# DAUGHTER_AUDIO.net
KiCad netlist of a schematic drawn in EAGLE
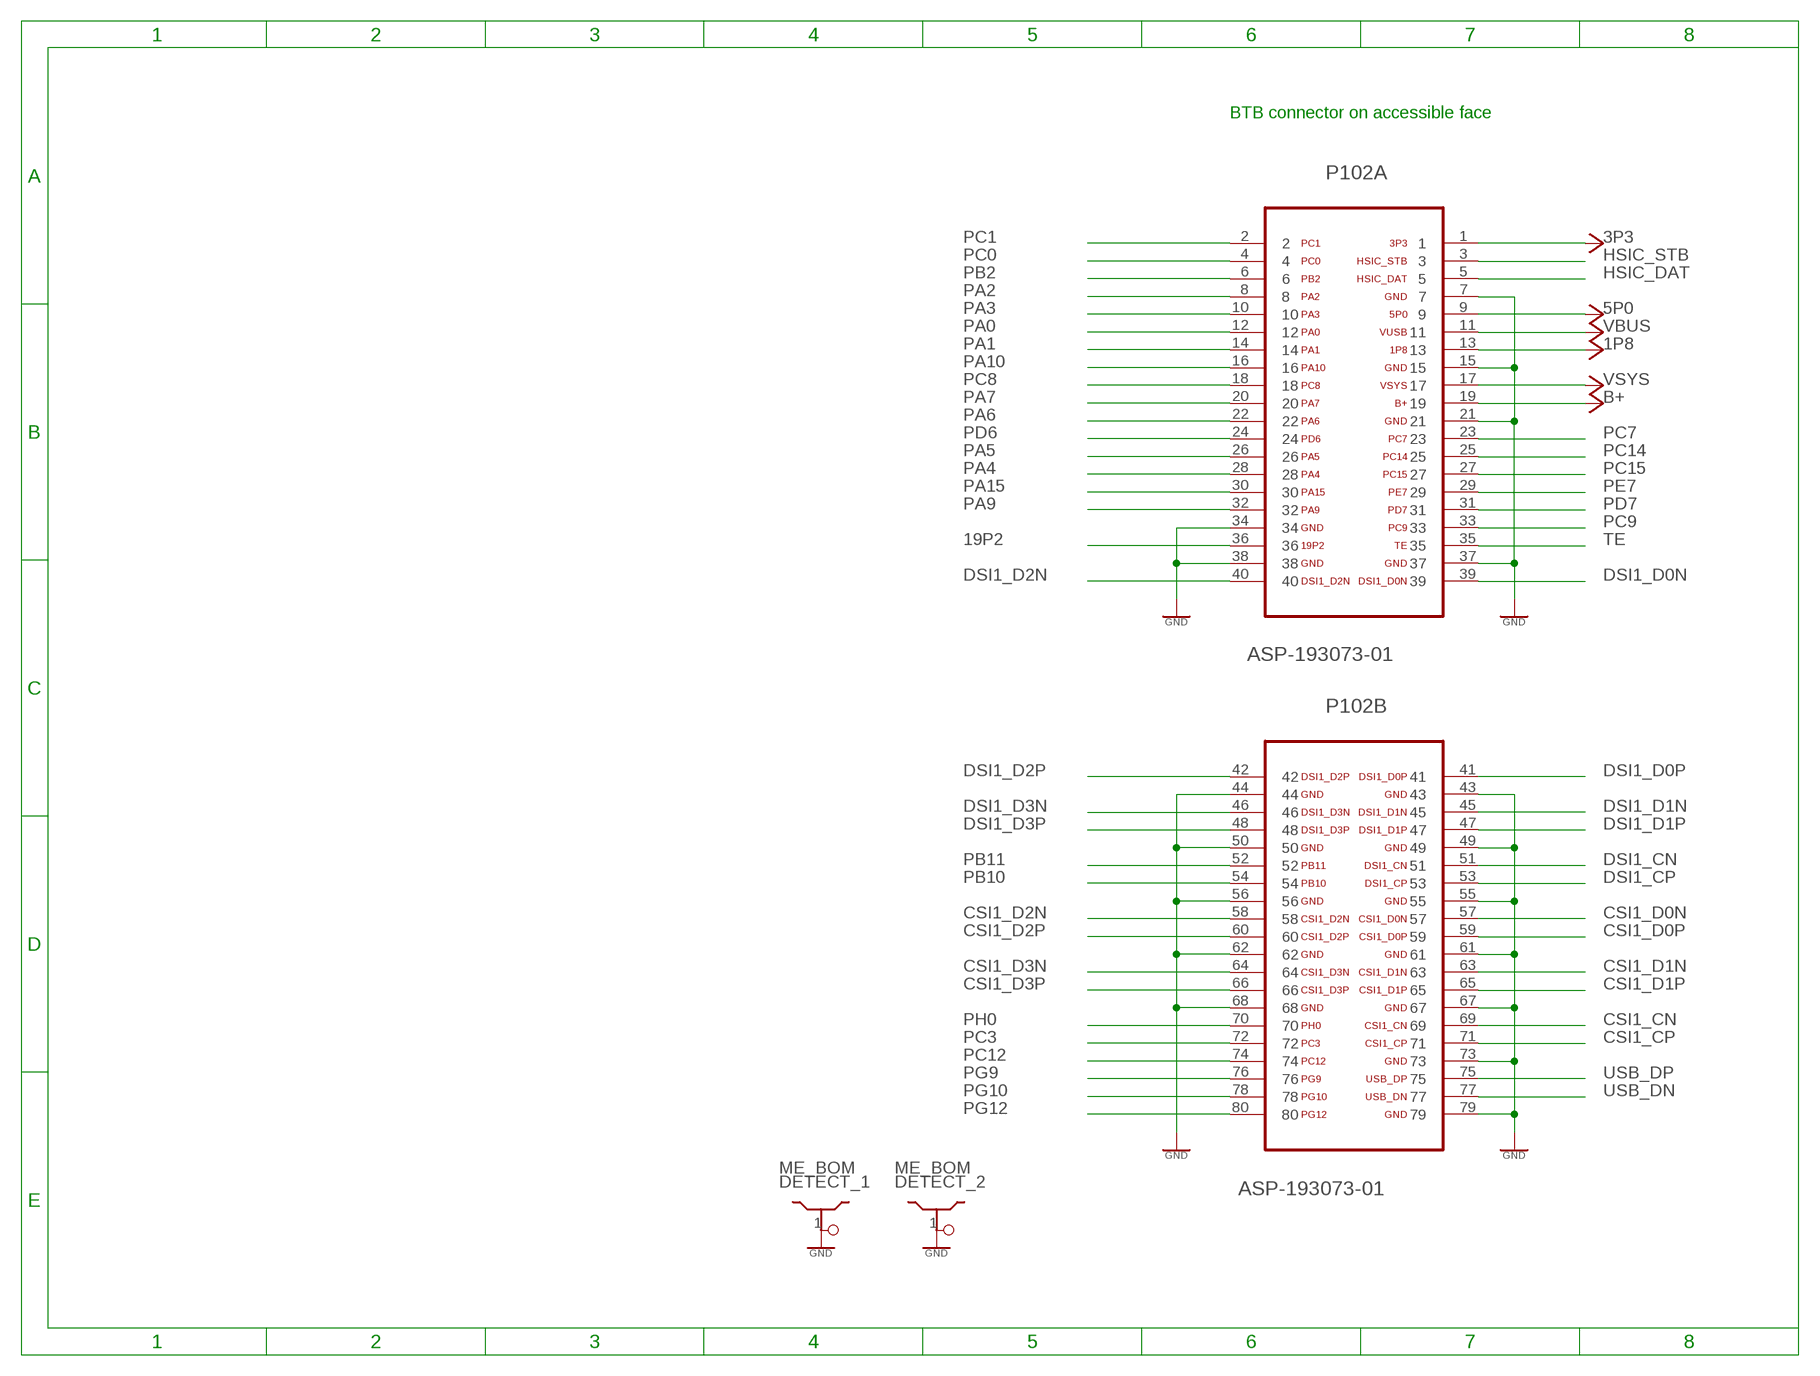
[diagram p0: schematic, sheet 1]
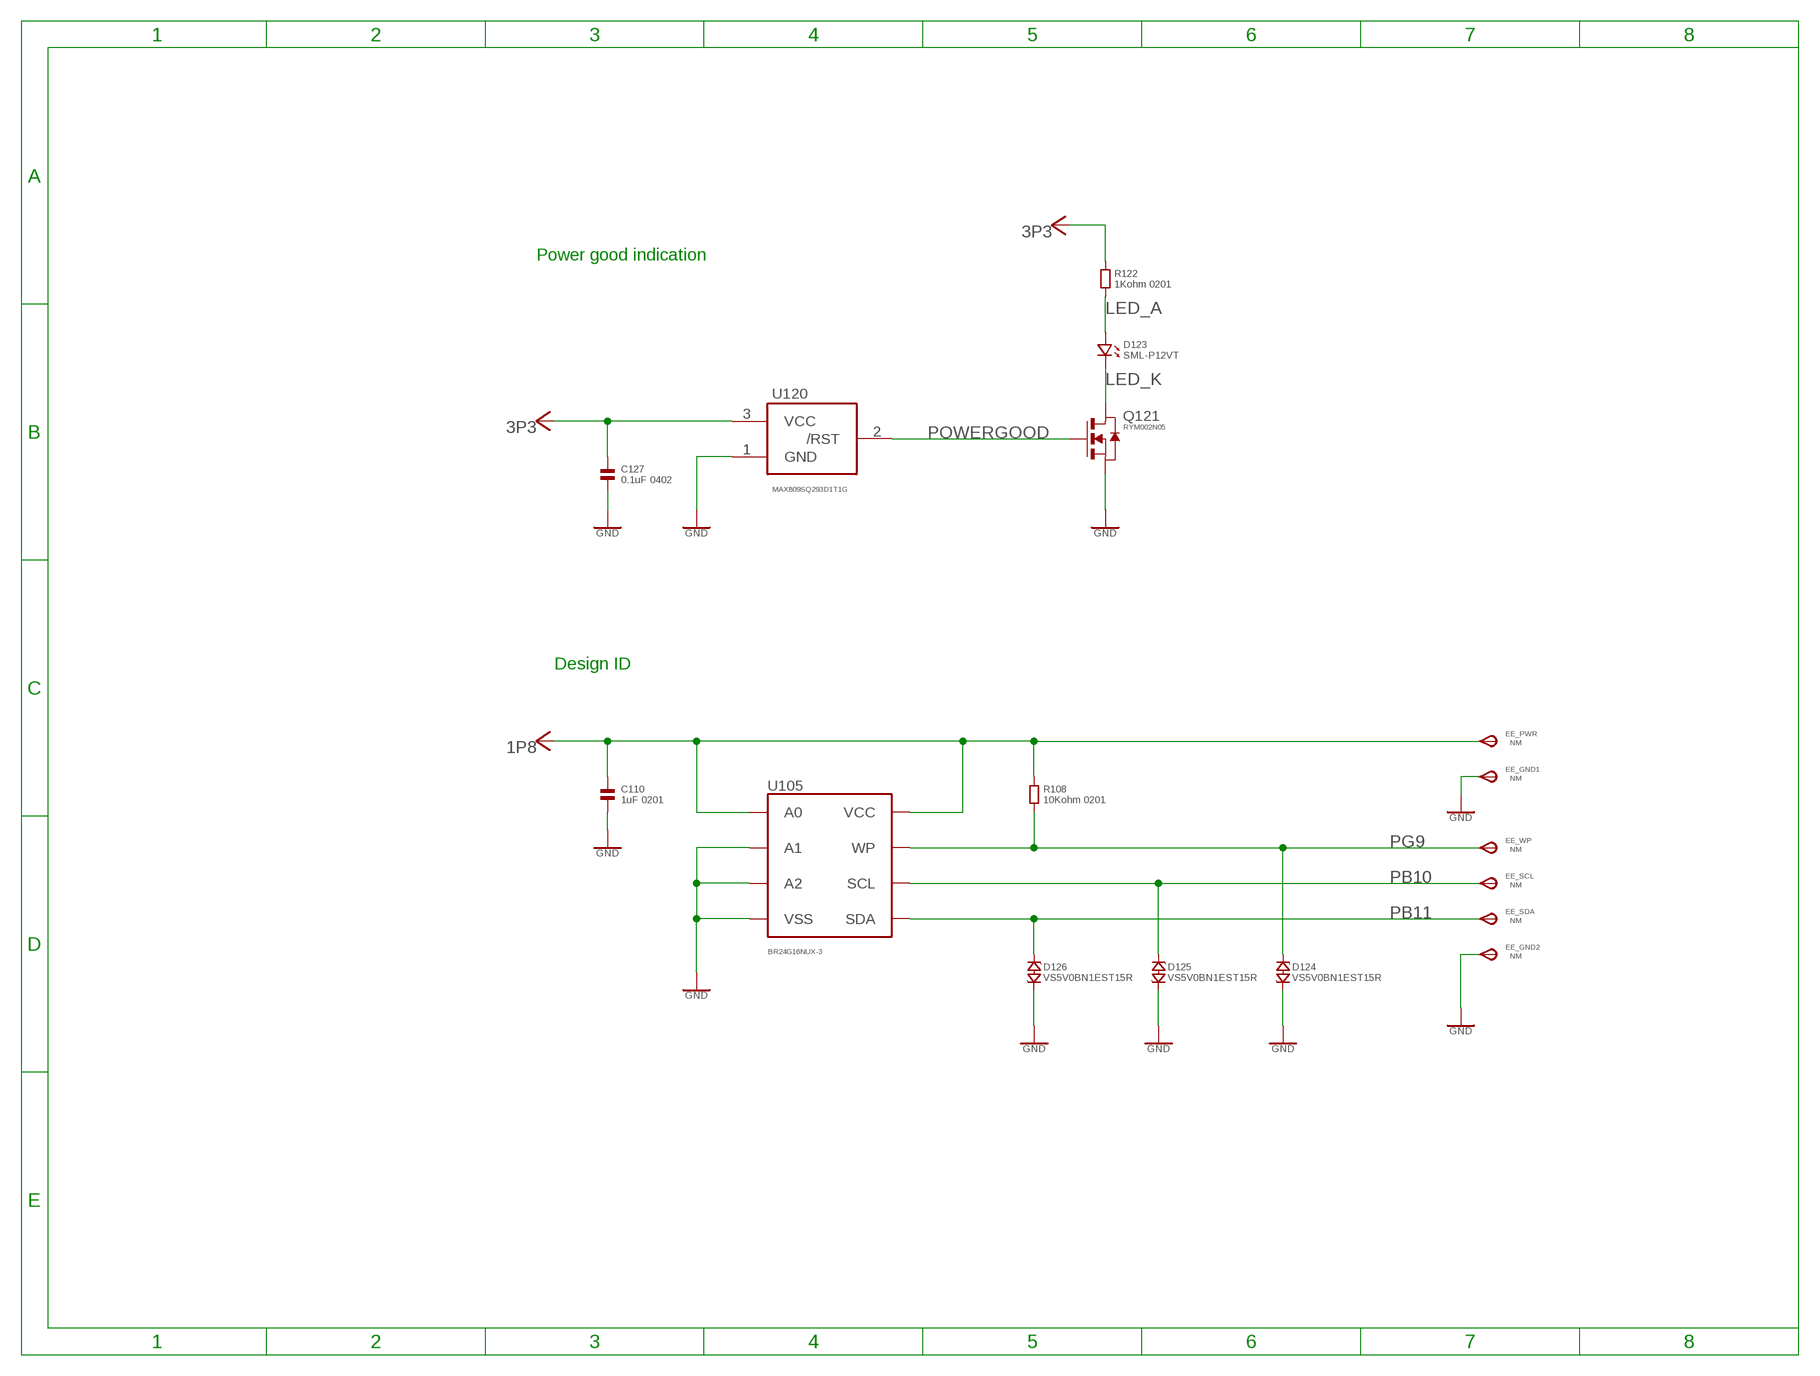
[diagram p1: schematic, sheet 2]
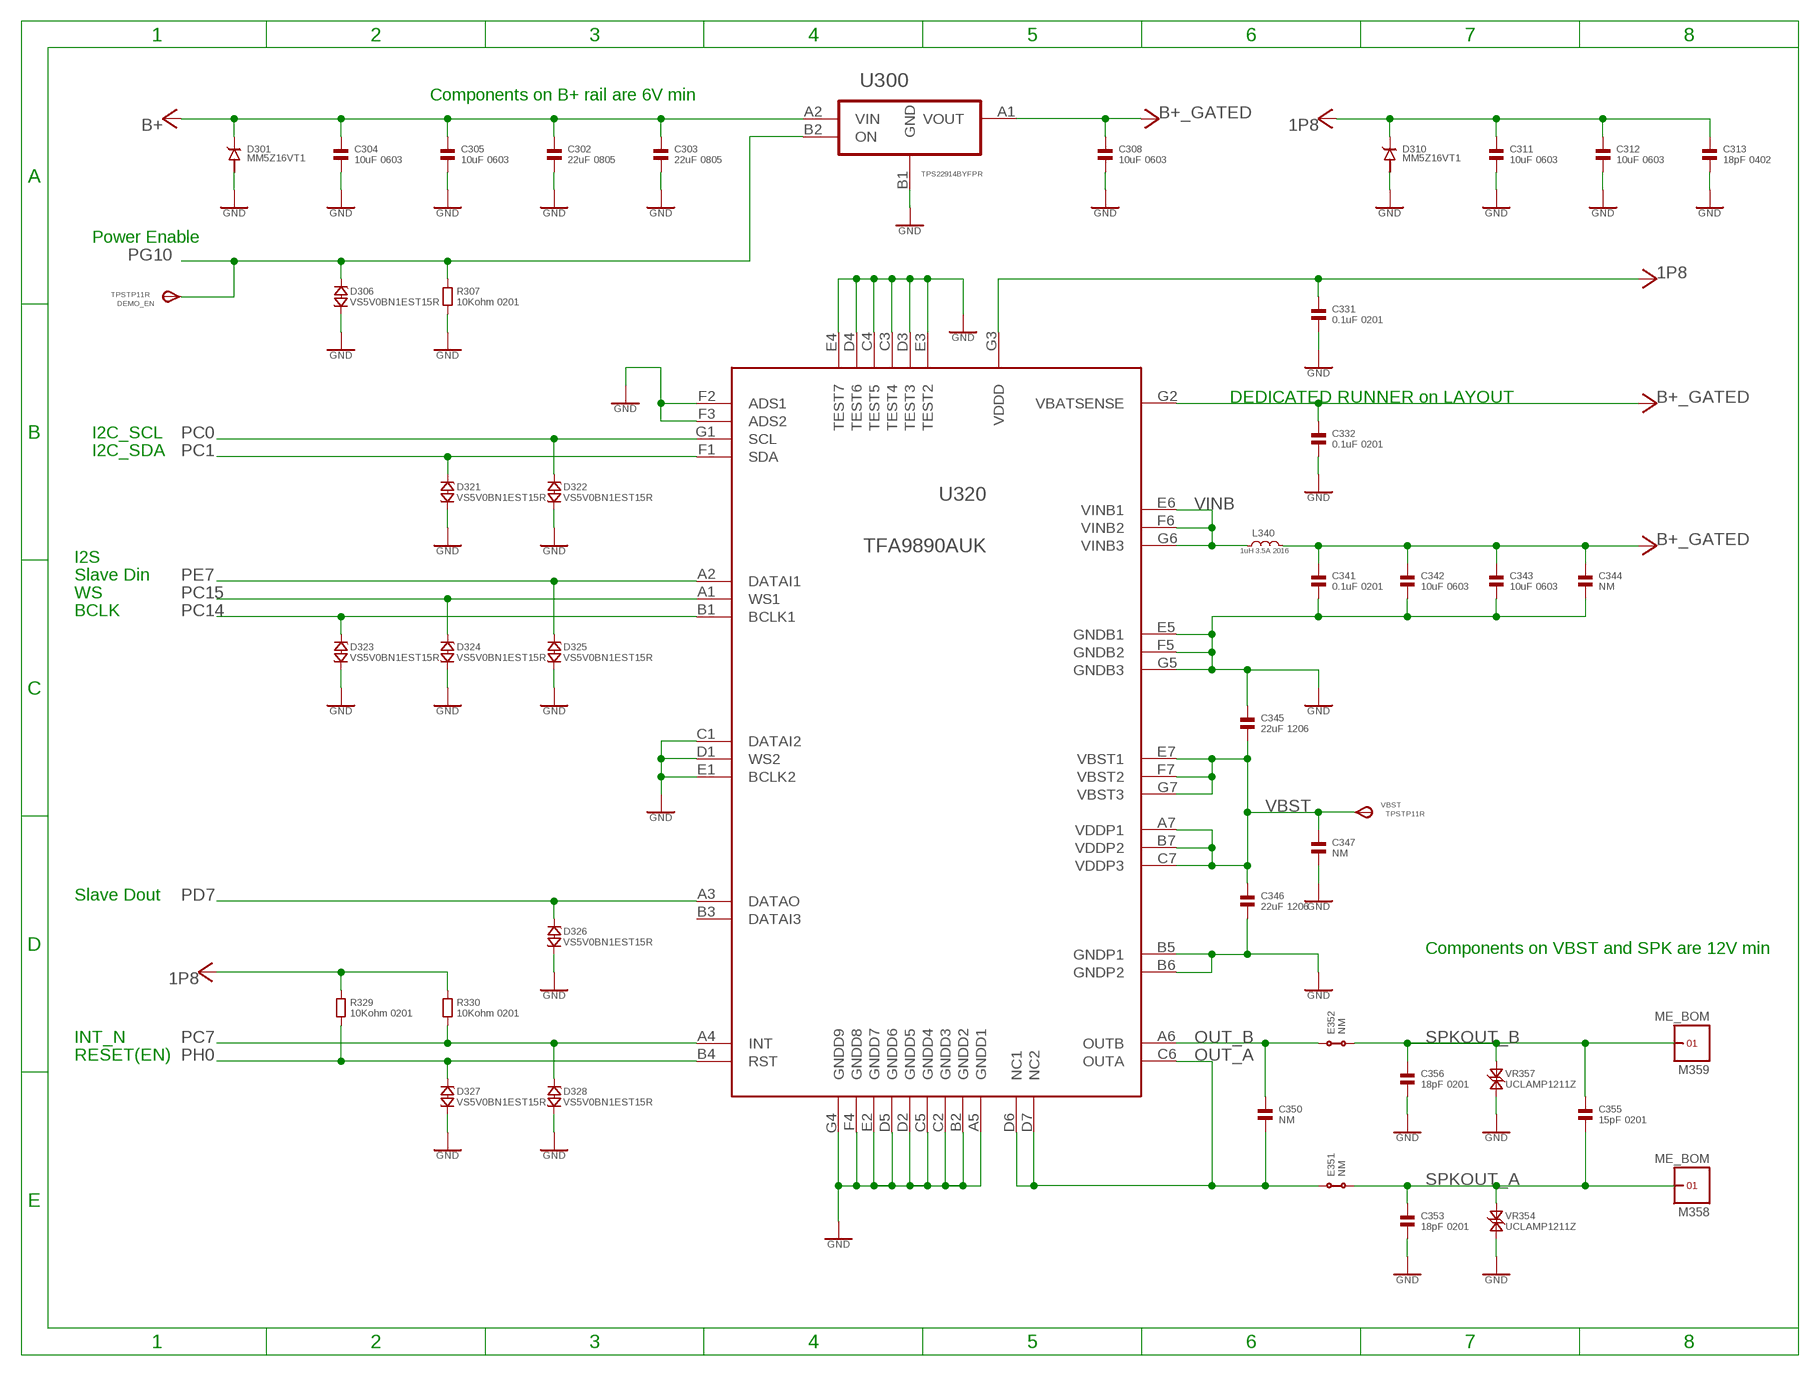
[diagram p2: schematic, sheet 3]

(export (version "E")
  (design (tool "Eeschema 10.0.6"))
  (components
    (comp (ref "C302")
      (value "22uF 0805")
      (footprint "eagle-import:0805")
      (libsource (lib "eagle-import") (part "CAPACITOR.0805"))
    )
    (comp (ref "C303")
      (value "22uF 0805")
      (footprint "eagle-import:0805")
      (libsource (lib "eagle-import") (part "CAPACITOR.0805"))
    )
    (comp (ref "C304")
      (value "10uF 0603")
      (footprint "eagle-import:0603")
      (libsource (lib "eagle-import") (part "CAPACITOR.0603"))
    )
    (comp (ref "C305")
      (value "10uF 0603")
      (footprint "eagle-import:0603")
      (libsource (lib "eagle-import") (part "CAPACITOR.0603"))
    )
    (comp (ref "C308")
      (value "10uF 0603")
      (footprint "eagle-import:0603")
      (libsource (lib "eagle-import") (part "CAPACITOR.0603"))
    )
    (comp (ref "C311")
      (value "10uF 0603")
      (footprint "eagle-import:0603")
      (libsource (lib "eagle-import") (part "CAPACITOR.0603"))
    )
    (comp (ref "C312")
      (value "10uF 0603")
      (footprint "eagle-import:0603")
      (libsource (lib "eagle-import") (part "CAPACITOR.0603"))
    )
    (comp (ref "C313")
      (value "18pF 0402")
      (footprint "eagle-import:0402")
      (libsource (lib "eagle-import") (part "CAPACITOR.0402"))
    )
    (comp (ref "C331")
      (value "0.1uF 0201")
      (footprint "eagle-import:0201")
      (libsource (lib "eagle-import") (part "CAPACITOR.0201"))
    )
    (comp (ref "C332")
      (value "0.1uF 0201")
      (footprint "eagle-import:0201")
      (libsource (lib "eagle-import") (part "CAPACITOR.0201"))
    )
    (comp (ref "C341")
      (value "0.1uF 0201")
      (footprint "eagle-import:0201")
      (libsource (lib "eagle-import") (part "CAPACITOR.0201"))
    )
    (comp (ref "C342")
      (value "10uF 0603")
      (footprint "eagle-import:0603")
      (libsource (lib "eagle-import") (part "CAPACITOR.0603"))
    )
    (comp (ref "C343")
      (value "10uF 0603")
      (footprint "eagle-import:0603")
      (libsource (lib "eagle-import") (part "CAPACITOR.0603"))
    )
    (comp (ref "C344")
      (value "NM")
      (footprint "eagle-import:0402")
      (libsource (lib "eagle-import") (part "CAPACITOR.0402"))
    )
    (comp (ref "C345")
      (value "22uF 1206")
      (footprint "eagle-import:1206")
      (libsource (lib "eagle-import") (part "CAPACITOR.1206"))
    )
    (comp (ref "C346")
      (value "22uF 1206")
      (footprint "eagle-import:1206")
      (libsource (lib "eagle-import") (part "CAPACITOR.1206"))
    )
    (comp (ref "C347")
      (value "NM")
      (footprint "eagle-import:0402")
      (libsource (lib "eagle-import") (part "CAPACITOR.0402"))
    )
    (comp (ref "C350")
      (value "NM")
      (footprint "eagle-import:0201")
      (libsource (lib "eagle-import") (part "CAPACITOR.0201"))
    )
    (comp (ref "C353")
      (value "18pF 0201")
      (footprint "eagle-import:0201")
      (libsource (lib "eagle-import") (part "CAPACITOR.0201"))
    )
    (comp (ref "C355")
      (value "15pF 0201")
      (footprint "eagle-import:0201")
      (libsource (lib "eagle-import") (part "CAPACITOR.0201"))
    )
    (comp (ref "C356")
      (value "18pF 0201")
      (footprint "eagle-import:0201")
      (libsource (lib "eagle-import") (part "CAPACITOR.0201"))
    )
    (comp (ref "D301")
      (value "MM5Z16VT1")
      (footprint "eagle-import:SOD523")
      (libsource (lib "eagle-import") (part "DIODE.SOD523"))
    )
    (comp (ref "D306")
      (value "VS5V0BN1EST15R")
      (footprint "eagle-import:CHIP_0201")
      (libsource (lib "eagle-import") (part "ESD_VARISTOR.0201"))
    )
    (comp (ref "D310")
      (value "MM5Z16VT1")
      (footprint "eagle-import:SOD523")
      (libsource (lib "eagle-import") (part "DIODE.SOD523"))
    )
    (comp (ref "D321")
      (value "VS5V0BN1EST15R")
      (footprint "eagle-import:CHIP_0201")
      (libsource (lib "eagle-import") (part "ESD_VARISTOR.0201"))
    )
    (comp (ref "D322")
      (value "VS5V0BN1EST15R")
      (footprint "eagle-import:CHIP_0201")
      (libsource (lib "eagle-import") (part "ESD_VARISTOR.0201"))
    )
    (comp (ref "D323")
      (value "VS5V0BN1EST15R")
      (footprint "eagle-import:CHIP_0201")
      (libsource (lib "eagle-import") (part "ESD_VARISTOR.0201"))
    )
    (comp (ref "D324")
      (value "VS5V0BN1EST15R")
      (footprint "eagle-import:CHIP_0201")
      (libsource (lib "eagle-import") (part "ESD_VARISTOR.0201"))
    )
    (comp (ref "D325")
      (value "VS5V0BN1EST15R")
      (footprint "eagle-import:CHIP_0201")
      (libsource (lib "eagle-import") (part "ESD_VARISTOR.0201"))
    )
    (comp (ref "D326")
      (value "VS5V0BN1EST15R")
      (footprint "eagle-import:CHIP_0201")
      (libsource (lib "eagle-import") (part "ESD_VARISTOR.0201"))
    )
    (comp (ref "D327")
      (value "VS5V0BN1EST15R")
      (footprint "eagle-import:CHIP_0201")
      (libsource (lib "eagle-import") (part "ESD_VARISTOR.0201"))
    )
    (comp (ref "D328")
      (value "VS5V0BN1EST15R")
      (footprint "eagle-import:CHIP_0201")
      (libsource (lib "eagle-import") (part "ESD_VARISTOR.0201"))
    )
    (comp (ref "DEMO_EN")
      (value "TPSTP11R")
      (footprint "eagle-import:TP11R")
      (libsource (lib "eagle-import") (part "TPSTP11R"))
    )
    (comp (ref "E351")
      (value "NM")
      (footprint "eagle-import:0603_SHORT")
      (libsource (lib "eagle-import") (part "SHORT_BAR.0603"))
    )
    (comp (ref "E352")
      (value "NM")
      (footprint "eagle-import:0603_SHORT")
      (libsource (lib "eagle-import") (part "SHORT_BAR.0603"))
    )
    (comp (ref "L340")
      (value "1uH 3.5A 2016")
      (footprint "eagle-import:2016")
      (libsource (lib "eagle-import") (part "POWER-INDUCTOR.2016"))
    )
    (comp (ref "M358")
      (value "ME_BOM")
      (footprint "eagle-import:PUCK")
      (fields (field (name "MPN") "refer to ME BOM"))
      (libsource (lib "eagle-import") (part "PUCK.PUCK"))
    )
    (comp (ref "M359")
      (value "ME_BOM")
      (footprint "eagle-import:PUCK")
      (fields (field (name "MPN") "refer to ME BOM"))
      (libsource (lib "eagle-import") (part "PUCK.PUCK"))
    )
    (comp (ref "R307")
      (value "10Kohm 0201")
      (footprint "eagle-import:0201")
      (libsource (lib "eagle-import") (part "RESISTOR.0201"))
    )
    (comp (ref "R329")
      (value "10Kohm 0201")
      (footprint "eagle-import:0201")
      (libsource (lib "eagle-import") (part "RESISTOR.0201"))
    )
    (comp (ref "R330")
      (value "10Kohm 0201")
      (footprint "eagle-import:0201")
      (libsource (lib "eagle-import") (part "RESISTOR.0201"))
    )
    (comp (ref "U300")
      (value "TPS22914BYFPR")
      (footprint "eagle-import:BGA0_75SQ_PS0_4_P4")
      (libsource (lib "eagle-import") (part "TPS22914BYFPR"))
    )
    (comp (ref "U320")
      (value "TFA9890AUK")
      (footprint "eagle-import:BGA7X7")
      (libsource (lib "eagle-import") (part "TFA9890AUK"))
    )
    (comp (ref "VBST")
      (value "TPSTP11R")
      (footprint "eagle-import:TP11R")
      (libsource (lib "eagle-import") (part "TPSTP11R"))
    )
    (comp (ref "VR354")
      (value "UCLAMP1211Z")
      (footprint "eagle-import:CHIP_0201")
      (libsource (lib "eagle-import") (part "ESD_TVS.0201"))
    )
    (comp (ref "VR357")
      (value "UCLAMP1211Z")
      (footprint "eagle-import:CHIP_0201")
      (libsource (lib "eagle-import") (part "ESD_TVS.0201"))
    )
    (comp (ref "DETECT_1")
      (value "ME_BOM")
      (footprint "eagle-import:PLUG")
      (fields (field (name "MPN") "refer to ME BOM"))
      (libsource (lib "eagle-import") (part "SHIELDDETECT"))
    )
    (comp (ref "DETECT_2")
      (value "ME_BOM")
      (footprint "eagle-import:PLUG")
      (fields (field (name "MPN") "refer to ME BOM"))
      (libsource (lib "eagle-import") (part "SHIELDDETECT"))
    )
    (comp (ref "P102")
      (value "ASP-193073-01")
      (footprint "eagle-import:FTMH-140-02-L-DV-ES-P-TR")
      (fields (field (name "MPN") "ASP-193073-01"))
      (libsource (lib "eagle-import") (part "FTMH-140-02-L-DV-ES-P-TR"))
    )
    (comp (ref "C110")
      (value "1uF 0201")
      (footprint "eagle-import:0201")
      (libsource (lib "eagle-import") (part "CAPACITOR.0201"))
    )
    (comp (ref "C127")
      (value "0.1uF 0402")
      (footprint "eagle-import:0402")
      (libsource (lib "eagle-import") (part "CAPACITOR.0402"))
    )
    (comp (ref "D123")
      (value "SML-P12VT")
      (footprint "eagle-import:0503.LED")
      (libsource (lib "eagle-import") (part "LED.0503"))
    )
    (comp (ref "D124")
      (value "VS5V0BN1EST15R")
      (footprint "eagle-import:CHIP_0201")
      (libsource (lib "eagle-import") (part "ESD_VARISTOR.0201"))
    )
    (comp (ref "D125")
      (value "VS5V0BN1EST15R")
      (footprint "eagle-import:CHIP_0201")
      (libsource (lib "eagle-import") (part "ESD_VARISTOR.0201"))
    )
    (comp (ref "D126")
      (value "VS5V0BN1EST15R")
      (footprint "eagle-import:CHIP_0201")
      (libsource (lib "eagle-import") (part "ESD_VARISTOR.0201"))
    )
    (comp (ref "EE_GND1")
      (value "NM")
      (footprint "eagle-import:TP11R")
      (libsource (lib "eagle-import") (part "TPSTP11R"))
    )
    (comp (ref "EE_GND2")
      (value "NM")
      (footprint "eagle-import:TP11R")
      (libsource (lib "eagle-import") (part "TPSTP11R"))
    )
    (comp (ref "EE_PWR")
      (value "NM")
      (footprint "eagle-import:TP11R")
      (libsource (lib "eagle-import") (part "TPSTP11R"))
    )
    (comp (ref "EE_SCL")
      (value "NM")
      (footprint "eagle-import:TP11R")
      (libsource (lib "eagle-import") (part "TPSTP11R"))
    )
    (comp (ref "EE_SDA")
      (value "NM")
      (footprint "eagle-import:TP11R")
      (libsource (lib "eagle-import") (part "TPSTP11R"))
    )
    (comp (ref "EE_WP")
      (value "NM")
      (footprint "eagle-import:TP11R")
      (libsource (lib "eagle-import") (part "TPSTP11R"))
    )
    (comp (ref "Q121")
      (value "RYM002N05")
      (footprint "eagle-import:VMT3")
      (libsource (lib "eagle-import") (part "FET-NRYM002N05"))
    )
    (comp (ref "R108")
      (value "10Kohm 0201")
      (footprint "eagle-import:0201")
      (libsource (lib "eagle-import") (part "RESISTOR.0201"))
    )
    (comp (ref "R122")
      (value "1Kohm 0201")
      (footprint "eagle-import:0201")
      (libsource (lib "eagle-import") (part "RESISTOR.0201"))
    )
    (comp (ref "U105")
      (value "BR24G16NUX-3")
      (footprint "eagle-import:DFN-8")
      (libsource (lib "eagle-import") (part "EEPROMDFN8"))
    )
    (comp (ref "U120")
      (value "MAX809SQ293D1T1G")
      (footprint "eagle-import:SC70-3L")
      (fields (field (name "MPN") "MAX809SQ293D1T1"))
      (libsource (lib "eagle-import") (part "MAX809"))
    )
  )
  (nets
    (net (code "1") (name "1P8") (class "Default")
      (node (ref "C110") (pin "1") (pinfunction "1_1") (pintype "bidirectional"))
      (node (ref "C311") (pin "1") (pinfunction "1_1") (pintype "bidirectional"))
      (node (ref "C312") (pin "1") (pinfunction "1_1") (pintype "bidirectional"))
      (node (ref "C313") (pin "1") (pinfunction "1_1") (pintype "bidirectional"))
      (node (ref "C331") (pin "1") (pinfunction "1_1") (pintype "bidirectional"))
      (node (ref "D310") (pin "1") (pinfunction "1_1") (pintype "bidirectional"))
      (node (ref "EE_PWR") (pin "TP") (pinfunction "PP_TP") (pintype "input"))
      (node (ref "P102") (pin "13") (pinfunction "13_13") (pintype "passive"))
      (node (ref "R108") (pin "1") (pinfunction "1_1") (pintype "bidirectional"))
      (node (ref "R329") (pin "1") (pinfunction "1_1") (pintype "bidirectional"))
      (node (ref "R330") (pin "1") (pinfunction "1_1") (pintype "bidirectional"))
      (node (ref "U105") (pin "P$1") (pinfunction "A0_P$1") (pintype "input"))
      (node (ref "U105") (pin "P$8") (pinfunction "VCC_P$8") (pintype "power_in"))
      (node (ref "U320") (pin "G3") (pinfunction "VDDD_G3") (pintype "bidirectional"))
    )
    (net (code "2") (name "3P3") (class "Default")
      (node (ref "C127") (pin "1") (pinfunction "1_1") (pintype "bidirectional"))
      (node (ref "P102") (pin "1") (pinfunction "1_1") (pintype "passive"))
      (node (ref "R122") (pin "1") (pinfunction "1_1") (pintype "bidirectional"))
      (node (ref "U120") (pin "3") (pinfunction "VCC_3") (pintype "input"))
    )
    (net (code "3") (name "5P0") (class "Default")
      (node (ref "P102") (pin "9") (pinfunction "9_9") (pintype "passive"))
    )
    (net (code "4") (name "19P2") (class "Default")
      (node (ref "P102") (pin "36") (pinfunction "36_36") (pintype "passive"))
    )
    (net (code "5") (name "B+") (class "Default")
      (node (ref "C302") (pin "1") (pinfunction "1_1") (pintype "bidirectional"))
      (node (ref "C303") (pin "1") (pinfunction "1_1") (pintype "bidirectional"))
      (node (ref "C304") (pin "1") (pinfunction "1_1") (pintype "bidirectional"))
      (node (ref "C305") (pin "1") (pinfunction "1_1") (pintype "bidirectional"))
      (node (ref "D301") (pin "1") (pinfunction "1_1") (pintype "bidirectional"))
      (node (ref "P102") (pin "19") (pinfunction "19_19") (pintype "passive"))
      (node (ref "U300") (pin "A2") (pinfunction "VIN_A2") (pintype "power_in"))
    )
    (net (code "6") (name "B+_GATED") (class "Default")
      (node (ref "C308") (pin "1") (pinfunction "1_1") (pintype "bidirectional"))
      (node (ref "C332") (pin "1") (pinfunction "1_1") (pintype "bidirectional"))
      (node (ref "C341") (pin "1") (pinfunction "1_1") (pintype "bidirectional"))
      (node (ref "C342") (pin "1") (pinfunction "1_1") (pintype "bidirectional"))
      (node (ref "C343") (pin "1") (pinfunction "1_1") (pintype "bidirectional"))
      (node (ref "C344") (pin "1") (pinfunction "1_1") (pintype "bidirectional"))
      (node (ref "L340") (pin "2") (pinfunction "2_2") (pintype "passive"))
      (node (ref "U300") (pin "A1") (pinfunction "VOUT_A1") (pintype "power_in"))
      (node (ref "U320") (pin "G2") (pinfunction "VBATSENSE_G2") (pintype "bidirectional"))
    )
    (net (code "7") (name "CSI1_CN") (class "Default")
      (node (ref "P102") (pin "69") (pinfunction "69_69") (pintype "passive"))
    )
    (net (code "8") (name "CSI1_CP") (class "Default")
      (node (ref "P102") (pin "71") (pinfunction "71_71") (pintype "passive"))
    )
    (net (code "9") (name "CSI1_D0N") (class "Default")
      (node (ref "P102") (pin "57") (pinfunction "57_57") (pintype "passive"))
    )
    (net (code "10") (name "CSI1_D0P") (class "Default")
      (node (ref "P102") (pin "59") (pinfunction "59_59") (pintype "passive"))
    )
    (net (code "11") (name "CSI1_D1N") (class "Default")
      (node (ref "P102") (pin "63") (pinfunction "63_63") (pintype "passive"))
    )
    (net (code "12") (name "CSI1_D1P") (class "Default")
      (node (ref "P102") (pin "65") (pinfunction "65_65") (pintype "passive"))
    )
    (net (code "13") (name "CSI1_D2N") (class "Default")
      (node (ref "P102") (pin "58") (pinfunction "58_58") (pintype "passive"))
    )
    (net (code "14") (name "CSI1_D2P") (class "Default")
      (node (ref "P102") (pin "60") (pinfunction "60_60") (pintype "passive"))
    )
    (net (code "15") (name "CSI1_D3N") (class "Default")
      (node (ref "P102") (pin "64") (pinfunction "64_64") (pintype "passive"))
    )
    (net (code "16") (name "CSI1_D3P") (class "Default")
      (node (ref "P102") (pin "66") (pinfunction "66_66") (pintype "passive"))
    )
    (net (code "17") (name "DSI1_CN") (class "Default")
      (node (ref "P102") (pin "51") (pinfunction "51_51") (pintype "passive"))
    )
    (net (code "18") (name "DSI1_CP") (class "Default")
      (node (ref "P102") (pin "53") (pinfunction "53_53") (pintype "passive"))
    )
    (net (code "19") (name "DSI1_D0N") (class "Default")
      (node (ref "P102") (pin "39") (pinfunction "39_39") (pintype "passive"))
    )
    (net (code "20") (name "DSI1_D0P") (class "Default")
      (node (ref "P102") (pin "41") (pinfunction "41_41") (pintype "passive"))
    )
    (net (code "21") (name "DSI1_D1N") (class "Default")
      (node (ref "P102") (pin "45") (pinfunction "45_45") (pintype "passive"))
    )
    (net (code "22") (name "DSI1_D1P") (class "Default")
      (node (ref "P102") (pin "47") (pinfunction "47_47") (pintype "passive"))
    )
    (net (code "23") (name "DSI1_D2N") (class "Default")
      (node (ref "P102") (pin "40") (pinfunction "40_40") (pintype "passive"))
    )
    (net (code "24") (name "DSI1_D2P") (class "Default")
      (node (ref "P102") (pin "42") (pinfunction "42_42") (pintype "passive"))
    )
    (net (code "25") (name "DSI1_D3N") (class "Default")
      (node (ref "P102") (pin "46") (pinfunction "46_46") (pintype "passive"))
    )
    (net (code "26") (name "DSI1_D3P") (class "Default")
      (node (ref "P102") (pin "48") (pinfunction "48_48") (pintype "passive"))
    )
    (net (code "27") (name "GND") (class "Default")
      (node (ref "C110") (pin "2") (pinfunction "2_2") (pintype "bidirectional"))
      (node (ref "C127") (pin "2") (pinfunction "2_2") (pintype "bidirectional"))
      (node (ref "C302") (pin "2") (pinfunction "2_2") (pintype "bidirectional"))
      (node (ref "C303") (pin "2") (pinfunction "2_2") (pintype "bidirectional"))
      (node (ref "C304") (pin "2") (pinfunction "2_2") (pintype "bidirectional"))
      (node (ref "C305") (pin "2") (pinfunction "2_2") (pintype "bidirectional"))
      (node (ref "C308") (pin "2") (pinfunction "2_2") (pintype "bidirectional"))
      (node (ref "C311") (pin "2") (pinfunction "2_2") (pintype "bidirectional"))
      (node (ref "C312") (pin "2") (pinfunction "2_2") (pintype "bidirectional"))
      (node (ref "C313") (pin "2") (pinfunction "2_2") (pintype "bidirectional"))
      (node (ref "C331") (pin "2") (pinfunction "2_2") (pintype "bidirectional"))
      (node (ref "C332") (pin "2") (pinfunction "2_2") (pintype "bidirectional"))
      (node (ref "C341") (pin "2") (pinfunction "2_2") (pintype "bidirectional"))
      (node (ref "C342") (pin "2") (pinfunction "2_2") (pintype "bidirectional"))
      (node (ref "C343") (pin "2") (pinfunction "2_2") (pintype "bidirectional"))
      (node (ref "C344") (pin "2") (pinfunction "2_2") (pintype "bidirectional"))
      (node (ref "C345") (pin "1") (pinfunction "1_1") (pintype "bidirectional"))
      (node (ref "C346") (pin "2") (pinfunction "2_2") (pintype "bidirectional"))
      (node (ref "C347") (pin "2") (pinfunction "2_2") (pintype "bidirectional"))
      (node (ref "C353") (pin "2") (pinfunction "2_2") (pintype "bidirectional"))
      (node (ref "C356") (pin "2") (pinfunction "2_2") (pintype "bidirectional"))
      (node (ref "D124") (pin "P$2") (pinfunction "2_P$2") (pintype "bidirectional"))
      (node (ref "D125") (pin "P$2") (pinfunction "2_P$2") (pintype "bidirectional"))
      (node (ref "D126") (pin "P$2") (pinfunction "2_P$2") (pintype "bidirectional"))
      (node (ref "D301") (pin "2") (pinfunction "2_2") (pintype "bidirectional"))
      (node (ref "D306") (pin "P$2") (pinfunction "2_P$2") (pintype "bidirectional"))
      (node (ref "D310") (pin "2") (pinfunction "2_2") (pintype "bidirectional"))
      (node (ref "D321") (pin "P$2") (pinfunction "2_P$2") (pintype "bidirectional"))
      (node (ref "D322") (pin "P$2") (pinfunction "2_P$2") (pintype "bidirectional"))
      (node (ref "D323") (pin "P$2") (pinfunction "2_P$2") (pintype "bidirectional"))
      (node (ref "D324") (pin "P$2") (pinfunction "2_P$2") (pintype "bidirectional"))
      (node (ref "D325") (pin "P$2") (pinfunction "2_P$2") (pintype "bidirectional"))
      (node (ref "D326") (pin "P$2") (pinfunction "2_P$2") (pintype "bidirectional"))
      (node (ref "D327") (pin "P$2") (pinfunction "2_P$2") (pintype "bidirectional"))
      (node (ref "D328") (pin "P$2") (pinfunction "2_P$2") (pintype "bidirectional"))
      (node (ref "DETECT_1") (pin "1") (pinfunction "1_1") (pintype "passive"))
      (node (ref "DETECT_2") (pin "1") (pinfunction "1_1") (pintype "passive"))
      (node (ref "EE_GND1") (pin "TP") (pinfunction "PP_TP") (pintype "input"))
      (node (ref "EE_GND2") (pin "TP") (pinfunction "PP_TP") (pintype "input"))
      (node (ref "P102") (pin "15") (pinfunction "15_15") (pintype "passive"))
      (node (ref "P102") (pin "21") (pinfunction "21_21") (pintype "passive"))
      (node (ref "P102") (pin "34") (pinfunction "34_34") (pintype "passive"))
      (node (ref "P102") (pin "37") (pinfunction "37_37") (pintype "passive"))
      (node (ref "P102") (pin "38") (pinfunction "38_38") (pintype "passive"))
      (node (ref "P102") (pin "43") (pinfunction "43_43") (pintype "passive"))
      (node (ref "P102") (pin "44") (pinfunction "44_44") (pintype "passive"))
      (node (ref "P102") (pin "49") (pinfunction "49_49") (pintype "passive"))
      (node (ref "P102") (pin "50") (pinfunction "50_50") (pintype "passive"))
      (node (ref "P102") (pin "55") (pinfunction "55_55") (pintype "passive"))
      (node (ref "P102") (pin "56") (pinfunction "56_56") (pintype "passive"))
      (node (ref "P102") (pin "61") (pinfunction "61_61") (pintype "passive"))
      (node (ref "P102") (pin "62") (pinfunction "62_62") (pintype "passive"))
      (node (ref "P102") (pin "67") (pinfunction "67_67") (pintype "passive"))
      (node (ref "P102") (pin "68") (pinfunction "68_68") (pintype "passive"))
      (node (ref "P102") (pin "7") (pinfunction "7_7") (pintype "passive"))
      (node (ref "P102") (pin "73") (pinfunction "73_73") (pintype "passive"))
      (node (ref "P102") (pin "79") (pinfunction "79_79") (pintype "passive"))
      (node (ref "Q121") (pin "2") (pinfunction "S_2") (pintype "passive"))
      (node (ref "R307") (pin "2") (pinfunction "2_2") (pintype "bidirectional"))
      (node (ref "U105") (pin "P$2") (pinfunction "A1_P$2") (pintype "input"))
      (node (ref "U105") (pin "P$3") (pinfunction "A2_P$3") (pintype "input"))
      (node (ref "U105") (pin "P$4") (pinfunction "VSS_P$4") (pintype "power_in"))
      (node (ref "U105") (pin "P$9") (pinfunction "VSS_P$9") (pintype "power_in"))
      (node (ref "U120") (pin "1") (pinfunction "GND_1") (pintype "power_in"))
      (node (ref "U300") (pin "B1") (pinfunction "GND_B1") (pintype "power_in"))
      (node (ref "U320") (pin "A5") (pinfunction "GNDD1_A5") (pintype "bidirectional"))
      (node (ref "U320") (pin "B2") (pinfunction "GNDD2_B2") (pintype "bidirectional"))
      (node (ref "U320") (pin "B5") (pinfunction "GNDP1_B5") (pintype "bidirectional"))
      (node (ref "U320") (pin "B6") (pinfunction "GNDP2_B6") (pintype "bidirectional"))
      (node (ref "U320") (pin "C1") (pinfunction "DATAI2_C1") (pintype "bidirectional"))
      (node (ref "U320") (pin "C2") (pinfunction "GNDD3_C2") (pintype "bidirectional"))
      (node (ref "U320") (pin "C3") (pinfunction "TEST4_C3") (pintype "bidirectional"))
      (node (ref "U320") (pin "C4") (pinfunction "TEST5_C4") (pintype "bidirectional"))
      (node (ref "U320") (pin "C5") (pinfunction "GNDD4_C5") (pintype "bidirectional"))
      (node (ref "U320") (pin "D1") (pinfunction "WS2_D1") (pintype "bidirectional"))
      (node (ref "U320") (pin "D2") (pinfunction "GNDD5_D2") (pintype "bidirectional"))
      (node (ref "U320") (pin "D3") (pinfunction "TEST3_D3") (pintype "bidirectional"))
      (node (ref "U320") (pin "D4") (pinfunction "TEST6_D4") (pintype "bidirectional"))
      (node (ref "U320") (pin "D5") (pinfunction "GNDD6_D5") (pintype "bidirectional"))
      (node (ref "U320") (pin "E1") (pinfunction "BCLK2_E1") (pintype "bidirectional"))
      (node (ref "U320") (pin "E2") (pinfunction "GNDD7_E2") (pintype "bidirectional"))
      (node (ref "U320") (pin "E3") (pinfunction "TEST2_E3") (pintype "bidirectional"))
      (node (ref "U320") (pin "E4") (pinfunction "TEST7_E4") (pintype "bidirectional"))
      (node (ref "U320") (pin "E5") (pinfunction "GNDB1_E5") (pintype "bidirectional"))
      (node (ref "U320") (pin "F2") (pinfunction "ADS1_F2") (pintype "bidirectional"))
      (node (ref "U320") (pin "F3") (pinfunction "ADS2_F3") (pintype "bidirectional"))
      (node (ref "U320") (pin "F4") (pinfunction "GNDD8_F4") (pintype "bidirectional"))
      (node (ref "U320") (pin "F5") (pinfunction "GNDB2_F5") (pintype "bidirectional"))
      (node (ref "U320") (pin "G4") (pinfunction "GNDD9_G4") (pintype "bidirectional"))
      (node (ref "U320") (pin "G5") (pinfunction "GNDB3_G5") (pintype "bidirectional"))
      (node (ref "VR354") (pin "P$2") (pinfunction "2_P$2") (pintype "bidirectional"))
      (node (ref "VR357") (pin "P$2") (pinfunction "2_P$2") (pintype "bidirectional"))
    )
    (net (code "28") (name "HSIC_DAT") (class "Default")
      (node (ref "P102") (pin "5") (pinfunction "5_5") (pintype "passive"))
    )
    (net (code "29") (name "HSIC_STB") (class "Default")
      (node (ref "P102") (pin "3") (pinfunction "3_3") (pintype "passive"))
    )
    (net (code "30") (name "LED_A") (class "Default")
      (node (ref "D123") (pin "P$1") (pinfunction "1_P$1") (pintype "bidirectional"))
      (node (ref "R122") (pin "2") (pinfunction "2_2") (pintype "bidirectional"))
    )
    (net (code "31") (name "LED_K") (class "Default")
      (node (ref "D123") (pin "P$2") (pinfunction "2_P$2") (pintype "bidirectional"))
      (node (ref "Q121") (pin "3") (pinfunction "D_3") (pintype "passive"))
    )
    (net (code "32") (name "OUT_A") (class "Default")
      (node (ref "C350") (pin "2") (pinfunction "2_2") (pintype "bidirectional"))
      (node (ref "E351") (pin "1") (pinfunction "1_1") (pintype "bidirectional"))
      (node (ref "U320") (pin "C6") (pinfunction "OUTA_C6") (pintype "bidirectional"))
      (node (ref "U320") (pin "D6") (pinfunction "NC1_D6") (pintype "bidirectional"))
      (node (ref "U320") (pin "D7") (pinfunction "NC2_D7") (pintype "bidirectional"))
    )
    (net (code "33") (name "OUT_B") (class "Default")
      (node (ref "C350") (pin "1") (pinfunction "1_1") (pintype "bidirectional"))
      (node (ref "E352") (pin "1") (pinfunction "1_1") (pintype "bidirectional"))
      (node (ref "U320") (pin "A6") (pinfunction "OUTB_A6") (pintype "bidirectional"))
    )
    (net (code "34") (name "PA0") (class "Default")
      (node (ref "P102") (pin "12") (pinfunction "12_12") (pintype "passive"))
    )
    (net (code "35") (name "PA1") (class "Default")
      (node (ref "P102") (pin "14") (pinfunction "14_14") (pintype "passive"))
    )
    (net (code "36") (name "PA2") (class "Default")
      (node (ref "P102") (pin "8") (pinfunction "8_8") (pintype "passive"))
    )
    (net (code "37") (name "PA3") (class "Default")
      (node (ref "P102") (pin "10") (pinfunction "10_10") (pintype "passive"))
    )
    (net (code "38") (name "PA4") (class "Default")
      (node (ref "P102") (pin "28") (pinfunction "28_28") (pintype "passive"))
    )
    (net (code "39") (name "PA5") (class "Default")
      (node (ref "P102") (pin "26") (pinfunction "26_26") (pintype "passive"))
    )
    (net (code "40") (name "PA6") (class "Default")
      (node (ref "P102") (pin "22") (pinfunction "22_22") (pintype "passive"))
    )
    (net (code "41") (name "PA7") (class "Default")
      (node (ref "P102") (pin "20") (pinfunction "20_20") (pintype "passive"))
    )
    (net (code "42") (name "PA9") (class "Default")
      (node (ref "P102") (pin "32") (pinfunction "32_32") (pintype "passive"))
    )
    (net (code "43") (name "PA10") (class "Default")
      (node (ref "P102") (pin "16") (pinfunction "16_16") (pintype "passive"))
    )
    (net (code "44") (name "PA15") (class "Default")
      (node (ref "P102") (pin "30") (pinfunction "30_30") (pintype "passive"))
    )
    (net (code "45") (name "PB2") (class "Default")
      (node (ref "P102") (pin "6") (pinfunction "6_6") (pintype "passive"))
    )
    (net (code "46") (name "PB10") (class "Default")
      (node (ref "D125") (pin "P$1") (pinfunction "1_P$1") (pintype "bidirectional"))
      (node (ref "EE_SCL") (pin "TP") (pinfunction "PP_TP") (pintype "input"))
      (node (ref "P102") (pin "54") (pinfunction "54_54") (pintype "passive"))
      (node (ref "U105") (pin "P$6") (pinfunction "SCL_P$6") (pintype "input"))
    )
    (net (code "47") (name "PB11") (class "Default")
      (node (ref "D126") (pin "P$1") (pinfunction "1_P$1") (pintype "bidirectional"))
      (node (ref "EE_SDA") (pin "TP") (pinfunction "PP_TP") (pintype "input"))
      (node (ref "P102") (pin "52") (pinfunction "52_52") (pintype "passive"))
      (node (ref "U105") (pin "P$5") (pinfunction "SDA_P$5") (pintype "bidirectional"))
    )
    (net (code "48") (name "PC0") (class "Default")
      (node (ref "D322") (pin "P$1") (pinfunction "1_P$1") (pintype "bidirectional"))
      (node (ref "P102") (pin "4") (pinfunction "4_4") (pintype "passive"))
      (node (ref "U320") (pin "G1") (pinfunction "SCL_G1") (pintype "bidirectional"))
    )
    (net (code "49") (name "PC1") (class "Default")
      (node (ref "D321") (pin "P$1") (pinfunction "1_P$1") (pintype "bidirectional"))
      (node (ref "P102") (pin "2") (pinfunction "2_2") (pintype "passive"))
      (node (ref "U320") (pin "F1") (pinfunction "SDA_F1") (pintype "bidirectional"))
    )
    (net (code "50") (name "PC3") (class "Default")
      (node (ref "P102") (pin "72") (pinfunction "72_72") (pintype "passive"))
    )
    (net (code "51") (name "PC7") (class "Default")
      (node (ref "D328") (pin "P$1") (pinfunction "1_P$1") (pintype "bidirectional"))
      (node (ref "P102") (pin "23") (pinfunction "23_23") (pintype "passive"))
      (node (ref "R330") (pin "2") (pinfunction "2_2") (pintype "bidirectional"))
      (node (ref "U320") (pin "A4") (pinfunction "INT_A4") (pintype "bidirectional"))
    )
    (net (code "52") (name "PC8") (class "Default")
      (node (ref "P102") (pin "18") (pinfunction "18_18") (pintype "passive"))
    )
    (net (code "53") (name "PC9") (class "Default")
      (node (ref "P102") (pin "33") (pinfunction "33_33") (pintype "passive"))
    )
    (net (code "54") (name "PC12") (class "Default")
      (node (ref "P102") (pin "74") (pinfunction "74_74") (pintype "passive"))
    )
    (net (code "55") (name "PC14") (class "Default")
      (node (ref "D323") (pin "P$1") (pinfunction "1_P$1") (pintype "bidirectional"))
      (node (ref "P102") (pin "25") (pinfunction "25_25") (pintype "passive"))
      (node (ref "U320") (pin "B1") (pinfunction "BCLK1_B1") (pintype "bidirectional"))
    )
    (net (code "56") (name "PC15") (class "Default")
      (node (ref "D324") (pin "P$1") (pinfunction "1_P$1") (pintype "bidirectional"))
      (node (ref "P102") (pin "27") (pinfunction "27_27") (pintype "passive"))
      (node (ref "U320") (pin "A1") (pinfunction "WS1_A1") (pintype "bidirectional"))
    )
    (net (code "57") (name "PD6") (class "Default")
      (node (ref "P102") (pin "24") (pinfunction "24_24") (pintype "passive"))
    )
    (net (code "58") (name "PD7") (class "Default")
      (node (ref "D326") (pin "P$1") (pinfunction "1_P$1") (pintype "bidirectional"))
      (node (ref "P102") (pin "31") (pinfunction "31_31") (pintype "passive"))
      (node (ref "U320") (pin "A3") (pinfunction "DATAO_A3") (pintype "bidirectional"))
    )
    (net (code "59") (name "PE7") (class "Default")
      (node (ref "D325") (pin "P$1") (pinfunction "1_P$1") (pintype "bidirectional"))
      (node (ref "P102") (pin "29") (pinfunction "29_29") (pintype "passive"))
      (node (ref "U320") (pin "A2") (pinfunction "DATAI1_A2") (pintype "bidirectional"))
    )
    (net (code "60") (name "PG9") (class "Default")
      (node (ref "D124") (pin "P$1") (pinfunction "1_P$1") (pintype "bidirectional"))
      (node (ref "EE_WP") (pin "TP") (pinfunction "PP_TP") (pintype "input"))
      (node (ref "P102") (pin "76") (pinfunction "76_76") (pintype "passive"))
      (node (ref "R108") (pin "2") (pinfunction "2_2") (pintype "bidirectional"))
      (node (ref "U105") (pin "P$7") (pinfunction "WP_P$7") (pintype "input"))
    )
    (net (code "61") (name "PG10") (class "Default")
      (node (ref "D306") (pin "P$1") (pinfunction "1_P$1") (pintype "bidirectional"))
      (node (ref "DEMO_EN") (pin "TP") (pinfunction "PP_TP") (pintype "input"))
      (node (ref "P102") (pin "78") (pinfunction "78_78") (pintype "passive"))
      (node (ref "R307") (pin "1") (pinfunction "1_1") (pintype "bidirectional"))
      (node (ref "U300") (pin "B2") (pinfunction "ON_B2") (pintype "input"))
    )
    (net (code "62") (name "PG12") (class "Default")
      (node (ref "P102") (pin "80") (pinfunction "80_80") (pintype "passive"))
    )
    (net (code "63") (name "PH0") (class "Default")
      (node (ref "D327") (pin "P$1") (pinfunction "1_P$1") (pintype "bidirectional"))
      (node (ref "P102") (pin "70") (pinfunction "70_70") (pintype "passive"))
      (node (ref "R329") (pin "2") (pinfunction "2_2") (pintype "bidirectional"))
      (node (ref "U320") (pin "B4") (pinfunction "RST_B4") (pintype "bidirectional"))
    )
    (net (code "64") (name "POWERGOOD") (class "Default")
      (node (ref "Q121") (pin "1") (pinfunction "G_1") (pintype "passive"))
      (node (ref "U120") (pin "2") (pinfunction "/RST_2") (pintype "output"))
    )
    (net (code "65") (name "SPKOUT_A") (class "Default")
      (node (ref "C353") (pin "1") (pinfunction "1_1") (pintype "bidirectional"))
      (node (ref "C355") (pin "2") (pinfunction "2_2") (pintype "bidirectional"))
      (node (ref "E351") (pin "2") (pinfunction "2_2") (pintype "bidirectional"))
      (node (ref "M358") (pin "1") (pinfunction "1_1") (pintype "bidirectional"))
      (node (ref "VR354") (pin "P$1") (pinfunction "1_P$1") (pintype "bidirectional"))
    )
    (net (code "66") (name "SPKOUT_B") (class "Default")
      (node (ref "C355") (pin "1") (pinfunction "1_1") (pintype "bidirectional"))
      (node (ref "C356") (pin "1") (pinfunction "1_1") (pintype "bidirectional"))
      (node (ref "E352") (pin "2") (pinfunction "2_2") (pintype "bidirectional"))
      (node (ref "M359") (pin "1") (pinfunction "1_1") (pintype "bidirectional"))
      (node (ref "VR357") (pin "P$1") (pinfunction "1_P$1") (pintype "bidirectional"))
    )
    (net (code "67") (name "TE") (class "Default")
      (node (ref "P102") (pin "35") (pinfunction "35_35") (pintype "passive"))
    )
    (net (code "68") (name "USB_DN") (class "Default")
      (node (ref "P102") (pin "77") (pinfunction "77_77") (pintype "passive"))
    )
    (net (code "69") (name "USB_DP") (class "Default")
      (node (ref "P102") (pin "75") (pinfunction "75_75") (pintype "passive"))
    )
    (net (code "70") (name "VBST") (class "Default")
      (node (ref "C345") (pin "2") (pinfunction "2_2") (pintype "bidirectional"))
      (node (ref "C346") (pin "1") (pinfunction "1_1") (pintype "bidirectional"))
      (node (ref "C347") (pin "1") (pinfunction "1_1") (pintype "bidirectional"))
      (node (ref "U320") (pin "A7") (pinfunction "VDDP1_A7") (pintype "bidirectional"))
      (node (ref "U320") (pin "B7") (pinfunction "VDDP2_B7") (pintype "bidirectional"))
      (node (ref "U320") (pin "C7") (pinfunction "VDDP3_C7") (pintype "bidirectional"))
      (node (ref "U320") (pin "E7") (pinfunction "VBST1_E7") (pintype "bidirectional"))
      (node (ref "U320") (pin "F7") (pinfunction "VBST2_F7") (pintype "bidirectional"))
      (node (ref "U320") (pin "G7") (pinfunction "VBST3_G7") (pintype "bidirectional"))
      (node (ref "VBST") (pin "TP") (pinfunction "PP_TP") (pintype "input"))
    )
    (net (code "71") (name "VBUS") (class "Default")
      (node (ref "P102") (pin "11") (pinfunction "11_11") (pintype "passive"))
    )
    (net (code "72") (name "VINB") (class "Default")
      (node (ref "L340") (pin "1") (pinfunction "1_1") (pintype "passive"))
      (node (ref "U320") (pin "E6") (pinfunction "VINB1_E6") (pintype "bidirectional"))
      (node (ref "U320") (pin "F6") (pinfunction "VINB2_F6") (pintype "bidirectional"))
      (node (ref "U320") (pin "G6") (pinfunction "VINB3_G6") (pintype "bidirectional"))
    )
    (net (code "73") (name "VSYS") (class "Default")
      (node (ref "P102") (pin "17") (pinfunction "17_17") (pintype "passive"))
    )
    (net (code "74") (name "unconnected-(U320-DATAI3-PadB3)") (class "Default")
      (node (ref "U320") (pin "B3") (pinfunction "DATAI3_B3") (pintype "bidirectional"))
    )
  )
)
